# DIO_4.net
KiCad netlist of a schematic drawn in Altium Designer
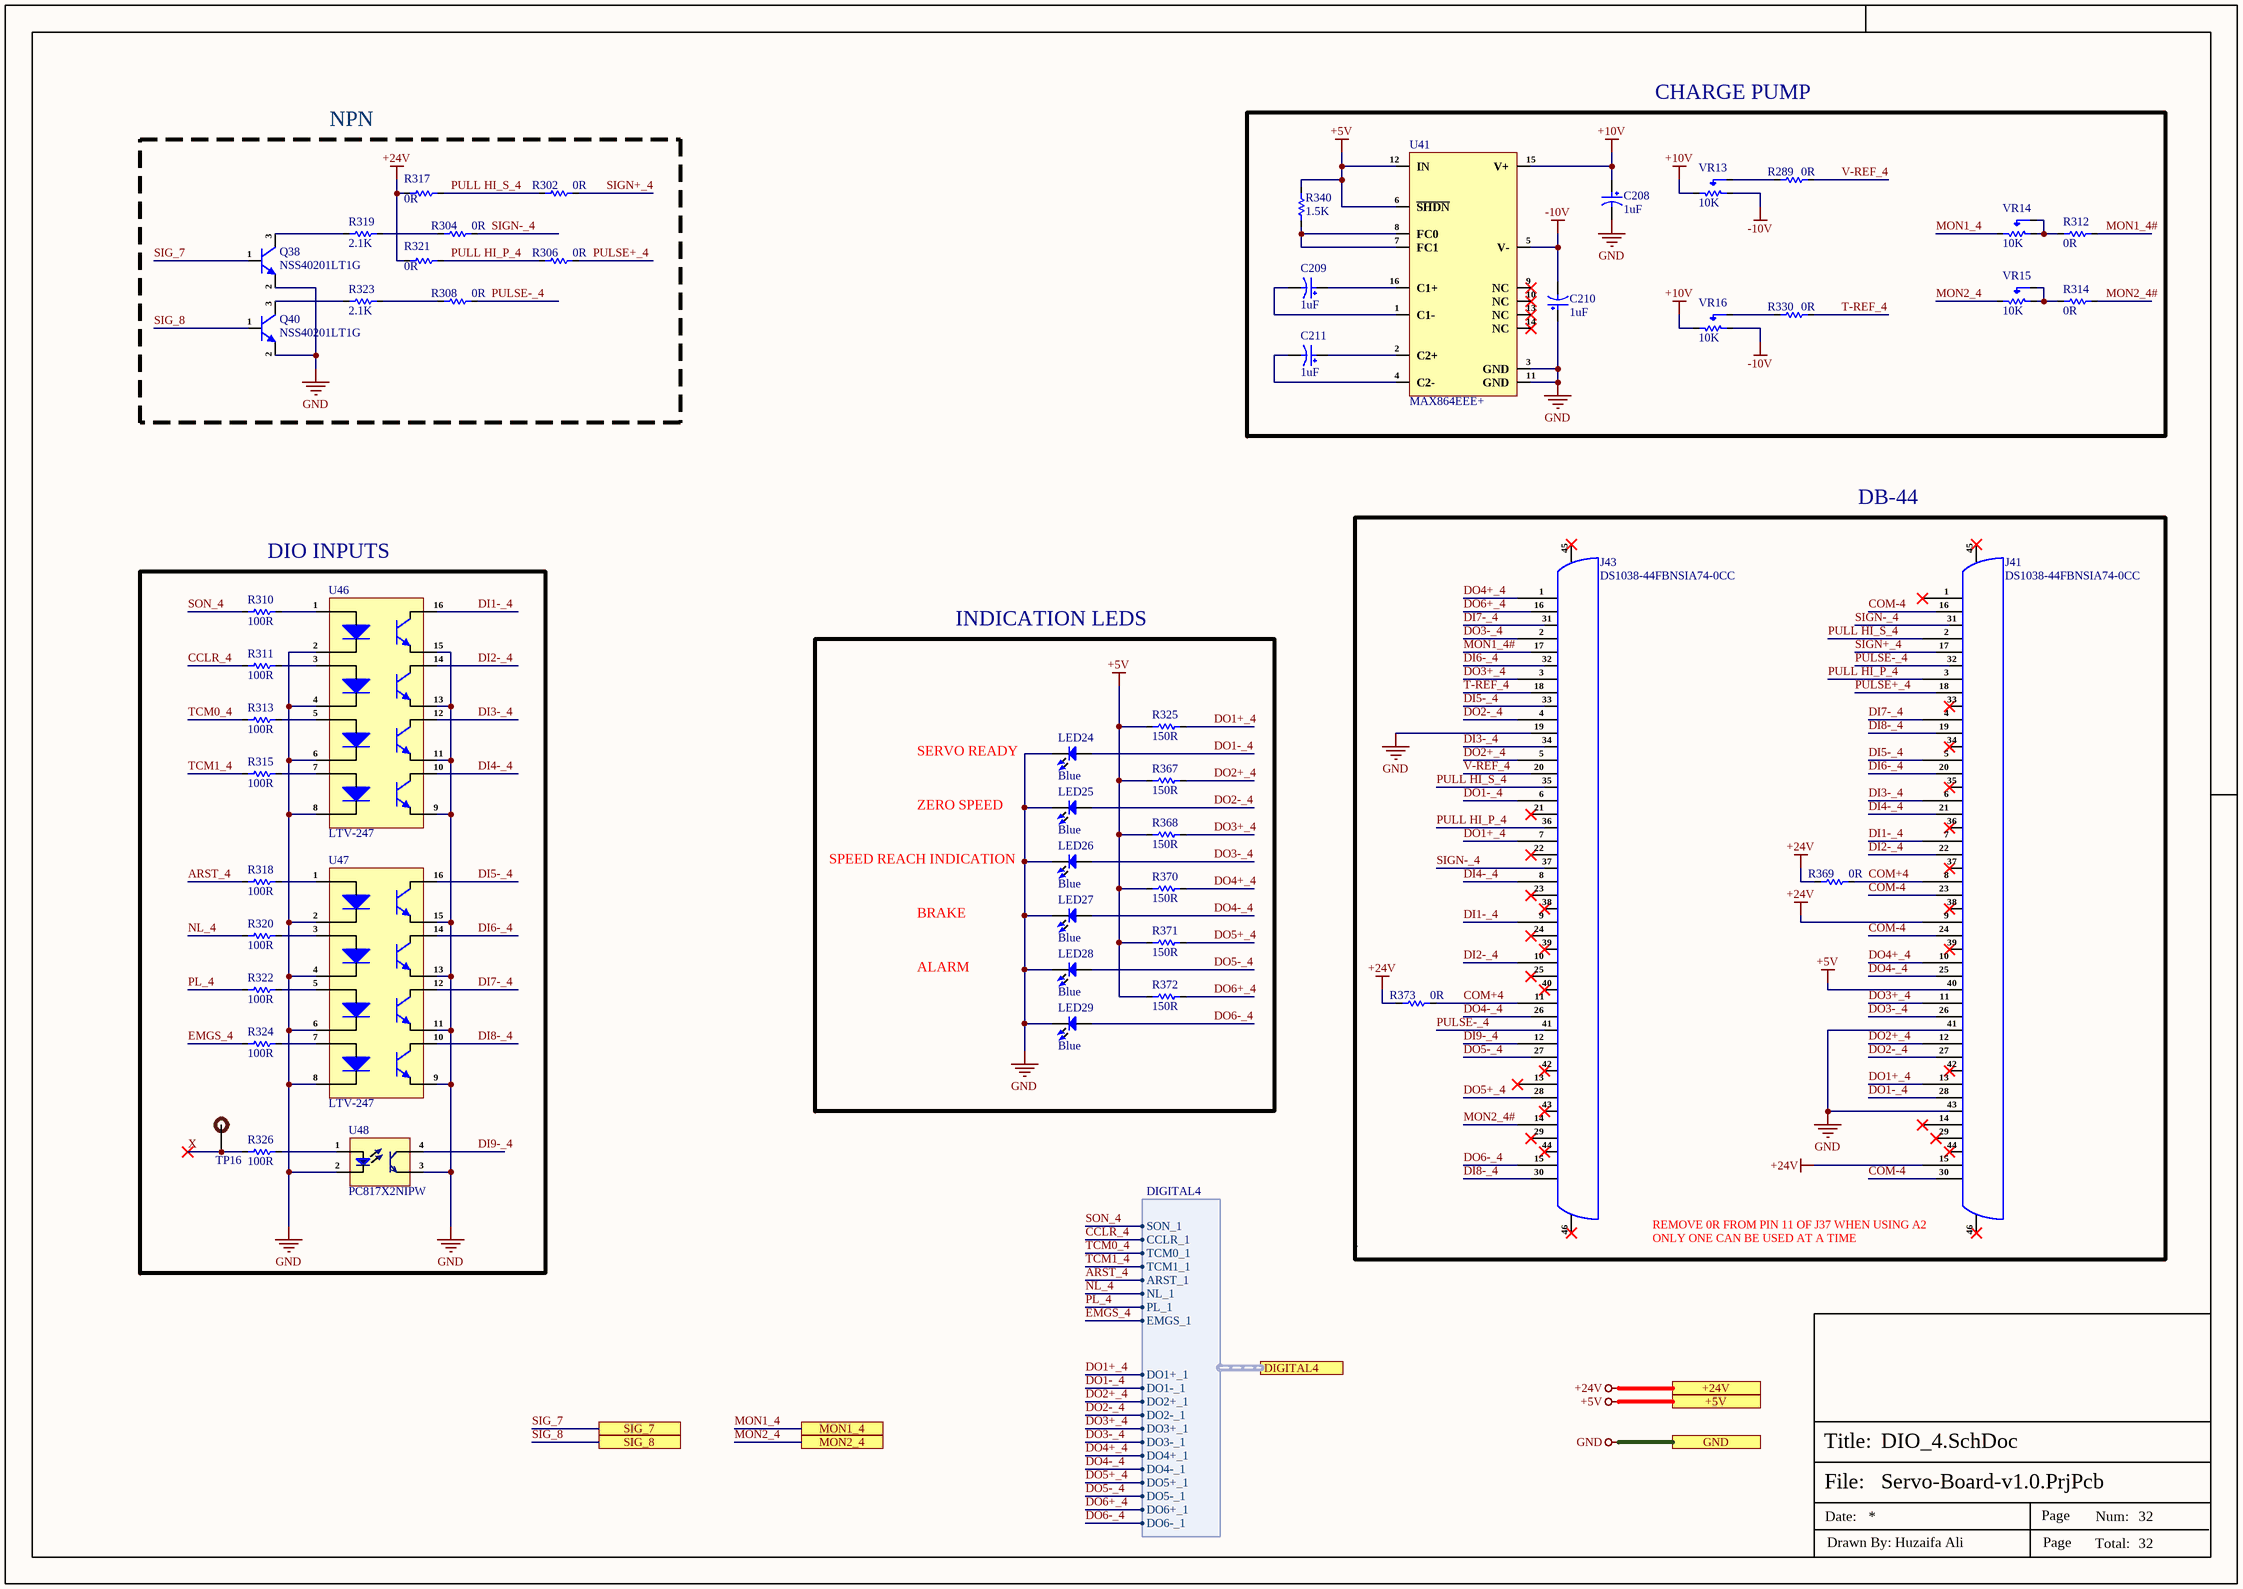
[diagram p0: DIO_4.SchDoc]

(export (version "E")
  (design (tool "Eeschema 10.0.6"))
  (components
    (comp (ref "C208")
      (value "1uF")
      (footprint "RVT1H1R0M0405")
      (description "1uF 50V 8mA@120Hz ±20% SMD,D4xL5.4mm Aluminum Electrolytic Capacitors - SMD ROHS")
      (fields (field (name "LCSC PART NUMBER") "C72491") (field (name "MANUFACTURER") "Roqang"))
      (libsource (lib "eSpark Libraries") (part "RVT1H1R0M0405"))
    )
    (comp (ref "C209")
      (value "1uF")
      (footprint "RVT1H1R0M0405")
      (description "1uF 50V 8mA@120Hz ±20% SMD,D4xL5.4mm Aluminum Electrolytic Capacitors - SMD ROHS")
      (fields (field (name "LCSC PART NUMBER") "C72491") (field (name "MANUFACTURER") "Roqang"))
      (libsource (lib "") (part "RVT1H1R0M0405_1"))
    )
    (comp (ref "C210")
      (value "1uF")
      (footprint "RVT1H1R0M0405")
      (description "1uF 50V 8mA@120Hz ±20% SMD,D4xL5.4mm Aluminum Electrolytic Capacitors - SMD ROHS")
      (fields (field (name "LCSC PART NUMBER") "C72491") (field (name "MANUFACTURER") "Roqang"))
      (libsource (lib "") (part "RVT1H1R0M0405_2"))
    )
    (comp (ref "C211")
      (value "1uF")
      (footprint "RVT1H1R0M0405")
      (description "1uF 50V 8mA@120Hz ±20% SMD,D4xL5.4mm Aluminum Electrolytic Capacitors - SMD ROHS")
      (fields (field (name "LCSC PART NUMBER") "C72491") (field (name "MANUFACTURER") "Roqang"))
      (libsource (lib "") (part "RVT1H1R0M0405_1"))
    )
    (comp (ref "J41")
      (value "DS1038-44FBNSIA74-0CC")
      (footprint "DS1038-44FBNSIA74-0CC")
      (description "44P Female D-Sub Right-Angle 3 1.5A -40℃~+105℃ Push-Pull D-Sub / VGA connector ROHS")
      (fields (field (name "MANUFACTURER") "CONNFLY Elec") (field (name "LCSC PART NUMBER") "C77844"))
      (libsource (lib "eSpark Libraries") (part "DS1038-44FBNSIA74-0CC"))
    )
    (comp (ref "J43")
      (value "DS1038-44FBNSIA74-0CC")
      (footprint "DS1038-44FBNSIA74-0CC")
      (description "44P Female D-Sub Right-Angle 3 1.5A -40℃~+105℃ Push-Pull D-Sub / VGA connector ROHS")
      (fields (field (name "MANUFACTURER") "CONNFLY Elec") (field (name "LCSC PART NUMBER") "C77844"))
      (libsource (lib "eSpark Libraries") (part "DS1038-44FBNSIA74-0CC"))
    )
    (comp (ref "LED24")
      (value "Blue")
      (footprint "LED-0603")
      (description "blue 0603 Light Emitting Diodes (LED) ROHS")
      (fields
        (field (name "MANUFACTURER") "Foshan NationStar Optoelectronics")
        (field (name "MANUFACTURER PART NUMBER") "NCD0603B3")
      )
      (libsource (lib "eSpark Libraries") (part "NCD0603B3"))
    )
    (comp (ref "LED25")
      (value "Blue")
      (footprint "LED-0603")
      (description "blue 0603 Light Emitting Diodes (LED) ROHS")
      (fields
        (field (name "MANUFACTURER") "Foshan NationStar Optoelectronics")
        (field (name "MANUFACTURER PART NUMBER") "NCD0603B3")
      )
      (libsource (lib "eSpark Libraries") (part "NCD0603B3"))
    )
    (comp (ref "LED26")
      (value "Blue")
      (footprint "LED-0603")
      (description "blue 0603 Light Emitting Diodes (LED) ROHS")
      (fields
        (field (name "MANUFACTURER") "Foshan NationStar Optoelectronics")
        (field (name "MANUFACTURER PART NUMBER") "NCD0603B3")
      )
      (libsource (lib "eSpark Libraries") (part "NCD0603B3"))
    )
    (comp (ref "LED27")
      (value "Blue")
      (footprint "LED-0603")
      (description "blue 0603 Light Emitting Diodes (LED) ROHS")
      (fields
        (field (name "MANUFACTURER") "Foshan NationStar Optoelectronics")
        (field (name "MANUFACTURER PART NUMBER") "NCD0603B3")
      )
      (libsource (lib "eSpark Libraries") (part "NCD0603B3"))
    )
    (comp (ref "LED28")
      (value "Blue")
      (footprint "LED-0603")
      (description "blue 0603 Light Emitting Diodes (LED) ROHS")
      (fields
        (field (name "MANUFACTURER") "Foshan NationStar Optoelectronics")
        (field (name "MANUFACTURER PART NUMBER") "NCD0603B3")
      )
      (libsource (lib "eSpark Libraries") (part "NCD0603B3"))
    )
    (comp (ref "LED29")
      (value "Blue")
      (footprint "LED-0603")
      (description "blue 0603 Light Emitting Diodes (LED) ROHS")
      (fields
        (field (name "MANUFACTURER") "Foshan NationStar Optoelectronics")
        (field (name "MANUFACTURER PART NUMBER") "NCD0603B3")
      )
      (libsource (lib "eSpark Libraries") (part "NCD0603B3"))
    )
    (comp (ref "Q38")
      (value "NSS40201LT1G")
      (footprint "SOT-23")
      (description "TRANS NPN 40V 2A SOT23-3")
      (fields (field (name "MANUFACTURER") "ON Semiconductor") (field (name "LCSC PART NUMBER") "C145175"))
      (libsource (lib "eSpark Libraries") (part "NSS40201LT1G"))
    )
    (comp (ref "Q40")
      (value "NSS40201LT1G")
      (footprint "SOT-23")
      (description "TRANS NPN 40V 2A SOT23-3")
      (fields (field (name "MANUFACTURER") "ON Semiconductor") (field (name "LCSC PART NUMBER") "C145175"))
      (libsource (lib "eSpark Libraries") (part "NSS40201LT1G"))
    )
    (comp (ref "R289")
      (value "0R")
      (footprint "Res-0402")
      (description "RES 0 OHM JUMPER 1/16W 0402")
      (fields
        (field (name "MANUFACTURER") "Yageo")
        (field (name "MANUFACTURER PART NUMBER") "RC0402FR-070RL")
      )
      (libsource (lib "eSpark Libraries") (part "RC0402FR-070RL"))
    )
    (comp (ref "R302")
      (value "0R")
      (footprint "Res-0603")
      (description "RES 0 OHM JUMPER 1/10W 0603")
      (fields
        (field (name "MANUFACTURER") "Yageo")
        (field (name "MANUFACTURER PART NUMBER") "RC0603JR-070RL")
      )
      (libsource (lib "eSpark Libraries") (part "RC0603JR-070RL"))
    )
    (comp (ref "R304")
      (value "0R")
      (footprint "Res-0603")
      (description "RES 0 OHM JUMPER 1/10W 0603")
      (fields
        (field (name "MANUFACTURER") "Yageo")
        (field (name "MANUFACTURER PART NUMBER") "RC0603JR-070RL")
      )
      (libsource (lib "eSpark Libraries") (part "RC0603JR-070RL"))
    )
    (comp (ref "R306")
      (value "0R")
      (footprint "Res-0603")
      (description "RES 0 OHM JUMPER 1/10W 0603")
      (fields
        (field (name "MANUFACTURER") "Yageo")
        (field (name "MANUFACTURER PART NUMBER") "RC0603JR-070RL")
      )
      (libsource (lib "eSpark Libraries") (part "RC0603JR-070RL"))
    )
    (comp (ref "R308")
      (value "0R")
      (footprint "Res-0603")
      (description "RES 0 OHM JUMPER 1/10W 0603")
      (fields
        (field (name "MANUFACTURER") "Yageo")
        (field (name "MANUFACTURER PART NUMBER") "RC0603JR-070RL")
      )
      (libsource (lib "eSpark Libraries") (part "RC0603JR-070RL"))
    )
    (comp (ref "R310")
      (value "100R")
      (footprint "Res-0402")
      (description "RES 100 OHM 1% 1/16W 0402")
      (fields
        (field (name "MANUFACTURER") "Yageo")
        (field (name "MANUFACTURER PART NUMBER") "RC0402FR-07100RL")
      )
      (libsource (lib "eSpark Libraries") (part "RC0402FR-07100RL"))
    )
    (comp (ref "R311")
      (value "100R")
      (footprint "Res-0402")
      (description "RES 100 OHM 1% 1/16W 0402")
      (fields
        (field (name "MANUFACTURER") "Yageo")
        (field (name "MANUFACTURER PART NUMBER") "RC0402FR-07100RL")
      )
      (libsource (lib "eSpark Libraries") (part "RC0402FR-07100RL"))
    )
    (comp (ref "R312")
      (value "0R")
      (footprint "Res-0402")
      (description "RES 0 OHM JUMPER 1/16W 0402")
      (fields
        (field (name "MANUFACTURER") "Yageo")
        (field (name "MANUFACTURER PART NUMBER") "RC0402FR-070RL")
      )
      (libsource (lib "eSpark Libraries") (part "RC0402FR-070RL"))
    )
    (comp (ref "R313")
      (value "100R")
      (footprint "Res-0402")
      (description "RES 100 OHM 1% 1/16W 0402")
      (fields
        (field (name "MANUFACTURER") "Yageo")
        (field (name "MANUFACTURER PART NUMBER") "RC0402FR-07100RL")
      )
      (libsource (lib "eSpark Libraries") (part "RC0402FR-07100RL"))
    )
    (comp (ref "R314")
      (value "0R")
      (footprint "Res-0402")
      (description "RES 0 OHM JUMPER 1/16W 0402")
      (fields
        (field (name "MANUFACTURER") "Yageo")
        (field (name "MANUFACTURER PART NUMBER") "RC0402FR-070RL")
      )
      (libsource (lib "eSpark Libraries") (part "RC0402FR-070RL"))
    )
    (comp (ref "R315")
      (value "100R")
      (footprint "Res-0402")
      (description "RES 100 OHM 1% 1/16W 0402")
      (fields
        (field (name "MANUFACTURER") "Yageo")
        (field (name "MANUFACTURER PART NUMBER") "RC0402FR-07100RL")
      )
      (libsource (lib "eSpark Libraries") (part "RC0402FR-07100RL"))
    )
    (comp (ref "R317")
      (value "0R")
      (footprint "Res-0603")
      (description "RES 0 OHM JUMPER 1/10W 0603")
      (fields
        (field (name "MANUFACTURER") "Yageo")
        (field (name "MANUFACTURER PART NUMBER") "RC0603JR-070RL")
      )
      (libsource (lib "eSpark Libraries") (part "RC0603JR-070RL"))
    )
    (comp (ref "R318")
      (value "100R")
      (footprint "Res-0402")
      (description "RES 100 OHM 1% 1/16W 0402")
      (fields
        (field (name "MANUFACTURER") "Yageo")
        (field (name "MANUFACTURER PART NUMBER") "RC0402FR-07100RL")
      )
      (libsource (lib "eSpark Libraries") (part "RC0402FR-07100RL"))
    )
    (comp (ref "R319")
      (value "2.1K")
      (footprint "Res-0603")
      (description "RES SMD 2.1K OHM 0.1% 1/10W 0603")
      (fields
        (field (name "MANUFACTURER") "Yageo")
        (field (name "MANUFACTURER PART NUMBER") "RT0603BRD072K1L")
      )
      (libsource (lib "eSpark Libraries") (part "RT0603BRD072K1L"))
    )
    (comp (ref "R320")
      (value "100R")
      (footprint "Res-0402")
      (description "RES 100 OHM 1% 1/16W 0402")
      (fields
        (field (name "MANUFACTURER") "Yageo")
        (field (name "MANUFACTURER PART NUMBER") "RC0402FR-07100RL")
      )
      (libsource (lib "eSpark Libraries") (part "RC0402FR-07100RL"))
    )
    (comp (ref "R321")
      (value "0R")
      (footprint "Res-0603")
      (description "RES 0 OHM JUMPER 1/10W 0603")
      (fields
        (field (name "MANUFACTURER") "Yageo")
        (field (name "MANUFACTURER PART NUMBER") "RC0603JR-070RL")
      )
      (libsource (lib "eSpark Libraries") (part "RC0603JR-070RL"))
    )
    (comp (ref "R322")
      (value "100R")
      (footprint "Res-0402")
      (description "RES 100 OHM 1% 1/16W 0402")
      (fields
        (field (name "MANUFACTURER") "Yageo")
        (field (name "MANUFACTURER PART NUMBER") "RC0402FR-07100RL")
      )
      (libsource (lib "eSpark Libraries") (part "RC0402FR-07100RL"))
    )
    (comp (ref "R323")
      (value "2.1K")
      (footprint "Res-0603")
      (description "RES SMD 2.1K OHM 0.1% 1/10W 0603")
      (fields
        (field (name "MANUFACTURER") "Yageo")
        (field (name "MANUFACTURER PART NUMBER") "RT0603BRD072K1L")
      )
      (libsource (lib "eSpark Libraries") (part "RT0603BRD072K1L"))
    )
    (comp (ref "R324")
      (value "100R")
      (footprint "Res-0402")
      (description "RES 100 OHM 1% 1/16W 0402")
      (fields
        (field (name "MANUFACTURER") "Yageo")
        (field (name "MANUFACTURER PART NUMBER") "RC0402FR-07100RL")
      )
      (libsource (lib "eSpark Libraries") (part "RC0402FR-07100RL"))
    )
    (comp (ref "R325")
      (value "150R")
      (footprint "Res-0603")
      (description "RES 150 OHM 0.5% 1/10W 0603")
      (fields
        (field (name "MANUFACTURER") "Yageo")
        (field (name "MANUFACTURER PART NUMBER") "RC0603DR-07150RL")
      )
      (libsource (lib "eSpark Libraries") (part "RC0603DR-07150RL"))
    )
    (comp (ref "R326")
      (value "100R")
      (footprint "Res-0402")
      (description "RES 100 OHM 1% 1/16W 0402")
      (fields
        (field (name "MANUFACTURER") "Yageo")
        (field (name "MANUFACTURER PART NUMBER") "RC0402FR-07100RL")
      )
      (libsource (lib "eSpark Libraries") (part "RC0402FR-07100RL"))
    )
    (comp (ref "R330")
      (value "0R")
      (footprint "Res-0402")
      (description "RES 0 OHM JUMPER 1/16W 0402")
      (fields
        (field (name "MANUFACTURER") "Yageo")
        (field (name "MANUFACTURER PART NUMBER") "RC0402FR-070RL")
      )
      (libsource (lib "eSpark Libraries") (part "RC0402FR-070RL"))
    )
    (comp (ref "R340")
      (value "1.5K")
      (footprint "Res-0402")
      (description "RES 1.5K OHM 1% 1/16W 0402")
      (fields
        (field (name "MANUFACTURER") "Yageo")
        (field (name "MANUFACTURER PART NUMBER") "RC0402FR-071K5L")
      )
      (libsource (lib "eSpark Libraries") (part "RC0402FR-071K5L"))
    )
    (comp (ref "R367")
      (value "150R")
      (footprint "Res-0603")
      (description "RES 150 OHM 0.5% 1/10W 0603")
      (fields
        (field (name "MANUFACTURER") "Yageo")
        (field (name "MANUFACTURER PART NUMBER") "RC0603DR-07150RL")
      )
      (libsource (lib "eSpark Libraries") (part "RC0603DR-07150RL"))
    )
    (comp (ref "R368")
      (value "150R")
      (footprint "Res-0603")
      (description "RES 150 OHM 0.5% 1/10W 0603")
      (fields
        (field (name "MANUFACTURER") "Yageo")
        (field (name "MANUFACTURER PART NUMBER") "RC0603DR-07150RL")
      )
      (libsource (lib "eSpark Libraries") (part "RC0603DR-07150RL"))
    )
    (comp (ref "R369")
      (value "0R")
      (footprint "Res-0402")
      (description "RES 0 OHM JUMPER 1/16W 0402")
      (fields
        (field (name "MANUFACTURER") "Yageo")
        (field (name "MANUFACTURER PART NUMBER") "RC0402FR-070RL")
      )
      (libsource (lib "eSpark Libraries") (part "RC0402FR-070RL"))
    )
    (comp (ref "R370")
      (value "150R")
      (footprint "Res-0603")
      (description "RES 150 OHM 0.5% 1/10W 0603")
      (fields
        (field (name "MANUFACTURER") "Yageo")
        (field (name "MANUFACTURER PART NUMBER") "RC0603DR-07150RL")
      )
      (libsource (lib "eSpark Libraries") (part "RC0603DR-07150RL"))
    )
    (comp (ref "R371")
      (value "150R")
      (footprint "Res-0603")
      (description "RES 150 OHM 0.5% 1/10W 0603")
      (fields
        (field (name "MANUFACTURER") "Yageo")
        (field (name "MANUFACTURER PART NUMBER") "RC0603DR-07150RL")
      )
      (libsource (lib "eSpark Libraries") (part "RC0603DR-07150RL"))
    )
    (comp (ref "R372")
      (value "150R")
      (footprint "Res-0603")
      (description "RES 150 OHM 0.5% 1/10W 0603")
      (fields
        (field (name "MANUFACTURER") "Yageo")
        (field (name "MANUFACTURER PART NUMBER") "RC0603DR-07150RL")
      )
      (libsource (lib "eSpark Libraries") (part "RC0603DR-07150RL"))
    )
    (comp (ref "R373")
      (value "0R")
      (footprint "Res-0402")
      (description "RES 0 OHM JUMPER 1/16W 0402")
      (fields
        (field (name "MANUFACTURER") "Yageo")
        (field (name "MANUFACTURER PART NUMBER") "RC0402FR-070RL")
      )
      (libsource (lib "eSpark Libraries") (part "RC0402FR-070RL"))
    )
    (comp (ref "TP16")
      (value "TEST POINT")
      (footprint "Test-point")
      (description "Test Point ON")
      (libsource (lib "eSpark Libraries") (part "TEST POINT"))
    )
    (comp (ref "U41")
      (value "MAX864EEE+")
      (footprint "16-QSOP")
      (description "IC REG CHARGE PUMP INV 16QSOP")
      (fields (field (name "MANUFACTURER") "Maxim"))
      (libsource (lib "eSpark Libraries") (part "MAX864EEE+"))
    )
    (comp (ref "U46")
      (value "LTV-247")
      (footprint "16-SO")
      (description "OPTOISO 3.75KV 4CH TRANS 16SO")
      (fields (field (name "MANUFACTURER") "Vishay Lite-On") (field (name "LCSC PART NUMBER") "C115451"))
      (libsource (lib "eSpark Libraries") (part "LTV-247"))
    )
    (comp (ref "U47")
      (value "LTV-247")
      (footprint "16-SO")
      (description "OPTOISO 3.75KV 4CH TRANS 16SO")
      (fields (field (name "MANUFACTURER") "Vishay Lite-On") (field (name "LCSC PART NUMBER") "C115451"))
      (libsource (lib "eSpark Libraries") (part "LTV-247"))
    )
    (comp (ref "U48")
      (value "PC817X2NIPW")
      (footprint "PC817X2NIPW")
      (description "Optoisolator Output Channel 4-SMD")
      (fields (field (name "MANUFACTURER") "Sharp") (field (name "LCSC PART NUMBER") "C2840443"))
      (libsource (lib "eSpark Libraries") (part "PC817X2NIPW"))
    )
    (comp (ref "VR13")
      (value "10K")
      (footprint "3362P-1-103")
      (description "TRIMMER 10K OHM 0.5W PC PIN TOP")
      (fields (field (name "LCSC PART NUMBER") "C118956") (field (name "MANUFACTURER") "Bourns"))
      (libsource (lib "eSpark Libraries") (part "3362P-1-103"))
    )
    (comp (ref "VR14")
      (value "10K")
      (footprint "3362P-1-103")
      (description "TRIMMER 10K OHM 0.5W PC PIN TOP")
      (fields (field (name "LCSC PART NUMBER") "C118956") (field (name "MANUFACTURER") "Bourns"))
      (libsource (lib "eSpark Libraries") (part "3362P-1-103"))
    )
    (comp (ref "VR15")
      (value "10K")
      (footprint "3362P-1-103")
      (description "TRIMMER 10K OHM 0.5W PC PIN TOP")
      (fields (field (name "LCSC PART NUMBER") "C118956") (field (name "MANUFACTURER") "Bourns"))
      (libsource (lib "eSpark Libraries") (part "3362P-1-103"))
    )
    (comp (ref "VR16")
      (value "10K")
      (footprint "3362P-1-103")
      (description "TRIMMER 10K OHM 0.5W PC PIN TOP")
      (fields (field (name "LCSC PART NUMBER") "C118956") (field (name "MANUFACTURER") "Bourns"))
      (libsource (lib "eSpark Libraries") (part "3362P-1-103"))
    )
  )
  (nets
    (net (code "2") (name "+5V") (class "Default")
      (node (ref "J41") (pin "40") (pinfunction "40_40") (pintype "passive"))
      (node (ref "R325") (pin "1") (pinfunction "1_1") (pintype "passive"))
      (node (ref "R340") (pin "2") (pinfunction "2_2") (pintype "passive"))
      (node (ref "R367") (pin "1") (pinfunction "1_1") (pintype "passive"))
      (node (ref "R368") (pin "1") (pinfunction "1_1") (pintype "passive"))
      (node (ref "R370") (pin "1") (pinfunction "1_1") (pintype "passive"))
      (node (ref "R371") (pin "1") (pinfunction "1_1") (pintype "passive"))
      (node (ref "R372") (pin "1") (pinfunction "1_1") (pintype "passive"))
      (node (ref "U41") (pin "12") (pinfunction "IN_12") (pintype "passive"))
      (node (ref "U41") (pin "6") (pinfunction "~{SHDN}_6") (pintype "passive"))
    )
    (net (code "3") (name "+10V") (class "Default")
      (node (ref "C208") (pin "1") (pintype "passive"))
      (node (ref "U41") (pin "15") (pinfunction "V+_15") (pintype "passive"))
      (node (ref "VR13") (pin "3") (pinfunction "CW_3") (pintype "passive"))
      (node (ref "VR16") (pin "3") (pinfunction "CW_3") (pintype "passive"))
    )
    (net (code "4") (name "+24V") (class "Default")
      (node (ref "J41") (pin "15") (pinfunction "15_15") (pintype "passive"))
      (node (ref "J41") (pin "9") (pinfunction "9_9") (pintype "passive"))
      (node (ref "R317") (pin "1") (pinfunction "1_1") (pintype "passive"))
      (node (ref "R321") (pin "1") (pinfunction "1_1") (pintype "passive"))
      (node (ref "R369") (pin "1") (pinfunction "1_1") (pintype "passive"))
      (node (ref "R373") (pin "1") (pinfunction "1_1") (pintype "passive"))
    )
    (net (code "5") (name "-10V") (class "Default")
      (node (ref "C210") (pin "2") (pintype "passive"))
      (node (ref "U41") (pin "5") (pinfunction "V-_5") (pintype "passive"))
      (node (ref "VR13") (pin "1") (pinfunction "CCW_1") (pintype "passive"))
      (node (ref "VR16") (pin "1") (pinfunction "CCW_1") (pintype "passive"))
    )
    (net (code "6") (name "/ARST_4") (class "Default")
      (node (ref "R318") (pin "1") (pinfunction "1_1") (pintype "passive"))
    )
    (net (code "7") (name "/CCLR_4") (class "Default")
      (node (ref "R311") (pin "1") (pinfunction "1_1") (pintype "passive"))
    )
    (net (code "8") (name "/COM+4") (class "Default")
      (node (ref "J41") (pin "8") (pinfunction "8_8") (pintype "passive"))
      (node (ref "J43") (pin "11") (pinfunction "11_11") (pintype "passive"))
      (node (ref "R369") (pin "2") (pinfunction "2_2") (pintype "passive"))
      (node (ref "R373") (pin "2") (pinfunction "2_2") (pintype "passive"))
    )
    (net (code "9") (name "/COM-4") (class "Default")
      (node (ref "J41") (pin "16") (pinfunction "16_16") (pintype "passive"))
      (node (ref "J41") (pin "23") (pinfunction "23_23") (pintype "passive"))
      (node (ref "J41") (pin "24") (pinfunction "24_24") (pintype "passive"))
      (node (ref "J41") (pin "30") (pinfunction "30_30") (pintype "passive"))
    )
    (net (code "10") (name "/DI1-_4") (class "Default")
      (node (ref "J41") (pin "7") (pinfunction "7_7") (pintype "passive"))
      (node (ref "J43") (pin "9") (pinfunction "9_9") (pintype "passive"))
      (node (ref "U46") (pin "16") (pinfunction "C_16") (pintype "passive"))
    )
    (net (code "11") (name "/DI2-_4") (class "Default")
      (node (ref "J41") (pin "22") (pinfunction "22_22") (pintype "passive"))
      (node (ref "J43") (pin "10") (pinfunction "10_10") (pintype "passive"))
      (node (ref "U46") (pin "14") (pinfunction "C_14") (pintype "passive"))
    )
    (net (code "12") (name "/DI3-_4") (class "Default")
      (node (ref "J41") (pin "6") (pinfunction "6_6") (pintype "passive"))
      (node (ref "J43") (pin "34") (pinfunction "34_34") (pintype "passive"))
      (node (ref "U46") (pin "12") (pinfunction "C_12") (pintype "passive"))
    )
    (net (code "13") (name "/DI4-_4") (class "Default")
      (node (ref "J41") (pin "21") (pinfunction "21_21") (pintype "passive"))
      (node (ref "J43") (pin "8") (pinfunction "8_8") (pintype "passive"))
      (node (ref "U46") (pin "10") (pinfunction "C_10") (pintype "passive"))
    )
    (net (code "14") (name "/DI5-_4") (class "Default")
      (node (ref "J41") (pin "5") (pinfunction "5_5") (pintype "passive"))
      (node (ref "J43") (pin "33") (pinfunction "33_33") (pintype "passive"))
      (node (ref "U47") (pin "16") (pinfunction "C_16") (pintype "passive"))
    )
    (net (code "15") (name "/DI6-_4") (class "Default")
      (node (ref "J41") (pin "20") (pinfunction "20_20") (pintype "passive"))
      (node (ref "J43") (pin "32") (pinfunction "32_32") (pintype "passive"))
      (node (ref "U47") (pin "14") (pinfunction "C_14") (pintype "passive"))
    )
    (net (code "16") (name "/DI7-_4") (class "Default")
      (node (ref "J41") (pin "4") (pinfunction "4_4") (pintype "passive"))
      (node (ref "J43") (pin "31") (pinfunction "31_31") (pintype "passive"))
      (node (ref "U47") (pin "12") (pinfunction "C_12") (pintype "passive"))
    )
    (net (code "17") (name "/DI8-_4") (class "Default")
      (node (ref "J41") (pin "19") (pinfunction "19_19") (pintype "passive"))
      (node (ref "J43") (pin "30") (pinfunction "30_30") (pintype "passive"))
      (node (ref "U47") (pin "10") (pinfunction "C_10") (pintype "passive"))
    )
    (net (code "18") (name "/DI9-_4") (class "Default")
      (node (ref "J43") (pin "12") (pinfunction "12_12") (pintype "passive"))
      (node (ref "U48") (pin "4") (pinfunction "C_4") (pintype "passive"))
    )
    (net (code "19") (name "/DO1+_4") (class "Default")
      (node (ref "J41") (pin "13") (pinfunction "13_13") (pintype "passive"))
      (node (ref "J43") (pin "7") (pinfunction "7_7") (pintype "passive"))
      (node (ref "R325") (pin "2") (pinfunction "2_2") (pintype "passive"))
    )
    (net (code "20") (name "/DO1-_4") (class "Default")
      (node (ref "J41") (pin "28") (pinfunction "28_28") (pintype "passive"))
      (node (ref "J43") (pin "6") (pinfunction "6_6") (pintype "passive"))
      (node (ref "LED24") (pin "1") (pinfunction "1_1") (pintype "passive"))
    )
    (net (code "21") (name "/DO2+_4") (class "Default")
      (node (ref "J41") (pin "12") (pinfunction "12_12") (pintype "passive"))
      (node (ref "J43") (pin "5") (pinfunction "5_5") (pintype "passive"))
      (node (ref "R367") (pin "2") (pinfunction "2_2") (pintype "passive"))
    )
    (net (code "22") (name "/DO2-_4") (class "Default")
      (node (ref "J41") (pin "27") (pinfunction "27_27") (pintype "passive"))
      (node (ref "J43") (pin "4") (pinfunction "4_4") (pintype "passive"))
      (node (ref "LED25") (pin "1") (pinfunction "1_1") (pintype "passive"))
    )
    (net (code "23") (name "/DO3+_4") (class "Default")
      (node (ref "J41") (pin "11") (pinfunction "11_11") (pintype "passive"))
      (node (ref "J43") (pin "3") (pinfunction "3_3") (pintype "passive"))
      (node (ref "R368") (pin "2") (pinfunction "2_2") (pintype "passive"))
    )
    (net (code "24") (name "/DO3-_4") (class "Default")
      (node (ref "J41") (pin "26") (pinfunction "26_26") (pintype "passive"))
      (node (ref "J43") (pin "2") (pinfunction "2_2") (pintype "passive"))
      (node (ref "LED26") (pin "1") (pinfunction "1_1") (pintype "passive"))
    )
    (net (code "25") (name "/DO4+_4") (class "Default")
      (node (ref "J41") (pin "10") (pinfunction "10_10") (pintype "passive"))
      (node (ref "J43") (pin "1") (pinfunction "1_1") (pintype "passive"))
      (node (ref "R370") (pin "2") (pinfunction "2_2") (pintype "passive"))
    )
    (net (code "26") (name "/DO4-_4") (class "Default")
      (node (ref "J41") (pin "25") (pinfunction "25_25") (pintype "passive"))
      (node (ref "J43") (pin "26") (pinfunction "26_26") (pintype "passive"))
      (node (ref "LED27") (pin "1") (pinfunction "1_1") (pintype "passive"))
    )
    (net (code "27") (name "/DO5+_4") (class "Default")
      (node (ref "J43") (pin "28") (pinfunction "28_28") (pintype "passive"))
      (node (ref "R371") (pin "2") (pinfunction "2_2") (pintype "passive"))
    )
    (net (code "28") (name "/DO5-_4") (class "Default")
      (node (ref "J43") (pin "27") (pinfunction "27_27") (pintype "passive"))
      (node (ref "LED28") (pin "1") (pinfunction "1_1") (pintype "passive"))
    )
    (net (code "29") (name "/DO6+_4") (class "Default")
      (node (ref "J43") (pin "16") (pinfunction "16_16") (pintype "passive"))
      (node (ref "R372") (pin "2") (pinfunction "2_2") (pintype "passive"))
    )
    (net (code "30") (name "/DO6-_4") (class "Default")
      (node (ref "J43") (pin "15") (pinfunction "15_15") (pintype "passive"))
      (node (ref "LED29") (pin "1") (pinfunction "1_1") (pintype "passive"))
    )
    (net (code "31") (name "/EMGS_4") (class "Default")
      (node (ref "R324") (pin "1") (pinfunction "1_1") (pintype "passive"))
    )
    (net (code "32") (name "/MON1_4") (class "Default")
      (node (ref "VR14") (pin "3") (pinfunction "CW_3") (pintype "passive"))
    )
    (net (code "33") (name "/MON1_4#") (class "Default")
      (node (ref "J43") (pin "17") (pinfunction "17_17") (pintype "passive"))
      (node (ref "R312") (pin "2") (pinfunction "2_2") (pintype "passive"))
    )
    (net (code "34") (name "/MON2_4") (class "Default")
      (node (ref "VR15") (pin "3") (pinfunction "CW_3") (pintype "passive"))
    )
    (net (code "35") (name "/MON2_4#") (class "Default")
      (node (ref "J43") (pin "14") (pinfunction "14_14") (pintype "passive"))
      (node (ref "R314") (pin "2") (pinfunction "2_2") (pintype "passive"))
    )
    (net (code "36") (name "/NL_4") (class "Default")
      (node (ref "R320") (pin "1") (pinfunction "1_1") (pintype "passive"))
    )
    (net (code "37") (name "/PL_4") (class "Default")
      (node (ref "R322") (pin "1") (pinfunction "1_1") (pintype "passive"))
    )
    (net (code "38") (name "/PULL HI_P_4") (class "Default")
      (node (ref "J41") (pin "3") (pinfunction "3_3") (pintype "passive"))
      (node (ref "J43") (pin "36") (pinfunction "36_36") (pintype "passive"))
      (node (ref "R306") (pin "1") (pinfunction "1_1") (pintype "passive"))
      (node (ref "R321") (pin "2") (pinfunction "2_2") (pintype "passive"))
    )
    (net (code "39") (name "/PULL HI_S_4") (class "Default")
      (node (ref "J41") (pin "2") (pinfunction "2_2") (pintype "passive"))
      (node (ref "J43") (pin "35") (pinfunction "35_35") (pintype "passive"))
      (node (ref "R302") (pin "1") (pinfunction "1_1") (pintype "passive"))
      (node (ref "R317") (pin "2") (pinfunction "2_2") (pintype "passive"))
    )
    (net (code "40") (name "/PULSE+_4") (class "Default")
      (node (ref "J41") (pin "18") (pinfunction "18_18") (pintype "passive"))
      (node (ref "R306") (pin "2") (pinfunction "2_2") (pintype "passive"))
    )
    (net (code "41") (name "/PULSE-_4") (class "Default")
      (node (ref "J41") (pin "32") (pinfunction "32_32") (pintype "passive"))
      (node (ref "J43") (pin "41") (pinfunction "41_41") (pintype "passive"))
      (node (ref "R308") (pin "2") (pinfunction "2_2") (pintype "passive"))
    )
    (net (code "42") (name "/SIGN+_4") (class "Default")
      (node (ref "J41") (pin "17") (pinfunction "17_17") (pintype "passive"))
      (node (ref "R302") (pin "2") (pinfunction "2_2") (pintype "passive"))
    )
    (net (code "43") (name "/SIGN-_4") (class "Default")
      (node (ref "J41") (pin "31") (pinfunction "31_31") (pintype "passive"))
      (node (ref "J43") (pin "37") (pinfunction "37_37") (pintype "passive"))
      (node (ref "R304") (pin "2") (pinfunction "2_2") (pintype "passive"))
    )
    (net (code "44") (name "/SIG_7") (class "Default")
      (node (ref "Q38") (pin "1") (pinfunction "B_1") (pintype "passive"))
    )
    (net (code "45") (name "/SIG_8") (class "Default")
      (node (ref "Q40") (pin "1") (pinfunction "B_1") (pintype "passive"))
    )
    (net (code "46") (name "/SON_4") (class "Default")
      (node (ref "R310") (pin "1") (pinfunction "1_1") (pintype "passive"))
    )
    (net (code "47") (name "/T-REF_4") (class "Default")
      (node (ref "J43") (pin "18") (pinfunction "18_18") (pintype "passive"))
      (node (ref "R330") (pin "2") (pinfunction "2_2") (pintype "passive"))
    )
    (net (code "48") (name "/TCM0_4") (class "Default")
      (node (ref "R313") (pin "1") (pinfunction "1_1") (pintype "passive"))
    )
    (net (code "49") (name "/TCM1_4") (class "Default")
      (node (ref "R315") (pin "1") (pinfunction "1_1") (pintype "passive"))
    )
    (net (code "50") (name "/V-REF_4") (class "Default")
      (node (ref "J43") (pin "20") (pinfunction "20_20") (pintype "passive"))
      (node (ref "R289") (pin "2") (pinfunction "2_2") (pintype "passive"))
    )
    (net (code "51") (name "/X") (class "Default")
      (node (ref "R326") (pin "1") (pinfunction "1_1") (pintype "passive"))
      (node (ref "TP16") (pin "1") (pinfunction "1_1") (pintype "passive"))
    )
    (net (code "53") (name "GND") (class "Default")
      (node (ref "C208") (pin "2") (pintype "passive"))
      (node (ref "C210") (pin "1") (pintype "passive"))
      (node (ref "J41") (pin "41") (pinfunction "41_41") (pintype "passive"))
      (node (ref "J41") (pin "43") (pinfunction "43_43") (pintype "passive"))
      (node (ref "J43") (pin "19") (pinfunction "19_19") (pintype "passive"))
      (node (ref "LED24") (pin "2") (pinfunction "2_2") (pintype "passive"))
      (node (ref "LED25") (pin "2") (pinfunction "2_2") (pintype "passive"))
      (node (ref "LED26") (pin "2") (pinfunction "2_2") (pintype "passive"))
      (node (ref "LED27") (pin "2") (pinfunction "2_2") (pintype "passive"))
      (node (ref "LED28") (pin "2") (pinfunction "2_2") (pintype "passive"))
      (node (ref "LED29") (pin "2") (pinfunction "2_2") (pintype "passive"))
      (node (ref "Q38") (pin "2") (pinfunction "E_2") (pintype "passive"))
      (node (ref "Q40") (pin "2") (pinfunction "E_2") (pintype "passive"))
      (node (ref "U41") (pin "11") (pinfunction "GND_11") (pintype "passive"))
      (node (ref "U41") (pin "3") (pinfunction "GND_3") (pintype "passive"))
      (node (ref "U46") (pin "11") (pinfunction "E_11") (pintype "passive"))
      (node (ref "U46") (pin "13") (pinfunction "E_13") (pintype "passive"))
      (node (ref "U46") (pin "15") (pinfunction "E_15") (pintype "passive"))
      (node (ref "U46") (pin "2") (pinfunction "K_2") (pintype "passive"))
      (node (ref "U46") (pin "4") (pinfunction "K_4") (pintype "passive"))
      (node (ref "U46") (pin "6") (pinfunction "K_6") (pintype "passive"))
      (node (ref "U46") (pin "8") (pinfunction "K_8") (pintype "passive"))
      (node (ref "U46") (pin "9") (pinfunction "E_9") (pintype "passive"))
      (node (ref "U47") (pin "11") (pinfunction "E_11") (pintype "passive"))
      (node (ref "U47") (pin "13") (pinfunction "E_13") (pintype "passive"))
      (node (ref "U47") (pin "15") (pinfunction "E_15") (pintype "passive"))
      (node (ref "U47") (pin "2") (pinfunction "K_2") (pintype "passive"))
      (node (ref "U47") (pin "4") (pinfunction "K_4") (pintype "passive"))
      (node (ref "U47") (pin "6") (pinfunction "K_6") (pintype "passive"))
      (node (ref "U47") (pin "8") (pinfunction "K_8") (pintype "passive"))
      (node (ref "U47") (pin "9") (pinfunction "E_9") (pintype "passive"))
      (node (ref "U48") (pin "2") (pinfunction "Ca_2") (pintype "passive"))
      (node (ref "U48") (pin "3") (pinfunction "E_3") (pintype "passive"))
    )
    (net (code "54") (name "Net-(Q38-C)") (class "Default")
      (node (ref "Q38") (pin "3") (pinfunction "C_3") (pintype "passive"))
      (node (ref "R319") (pin "1") (pinfunction "1_1") (pintype "passive"))
    )
    (net (code "55") (name "Net-(Q40-C)") (class "Default")
      (node (ref "Q40") (pin "3") (pinfunction "C_3") (pintype "passive"))
      (node (ref "R323") (pin "1") (pinfunction "1_1") (pintype "passive"))
    )
    (net (code "56") (name "Net-(R304-Pad1)") (class "Default")
      (node (ref "R304") (pin "1") (pinfunction "1_1") (pintype "passive"))
      (node (ref "R319") (pin "2") (pinfunction "2_2") (pintype "passive"))
    )
    (net (code "57") (name "Net-(R308-Pad1)") (class "Default")
      (node (ref "R308") (pin "1") (pinfunction "1_1") (pintype "passive"))
      (node (ref "R323") (pin "2") (pinfunction "2_2") (pintype "passive"))
    )
    (net (code "58") (name "Net-(R310-Pad2)") (class "Default")
      (node (ref "R310") (pin "2") (pinfunction "2_2") (pintype "passive"))
      (node (ref "U46") (pin "1") (pinfunction "A_1") (pintype "passive"))
    )
    (net (code "59") (name "Net-(R311-Pad2)") (class "Default")
      (node (ref "R311") (pin "2") (pinfunction "2_2") (pintype "passive"))
      (node (ref "U46") (pin "3") (pinfunction "A_3") (pintype "passive"))
    )
    (net (code "60") (name "Net-(R313-Pad2)") (class "Default")
      (node (ref "R313") (pin "2") (pinfunction "2_2") (pintype "passive"))
      (node (ref "U46") (pin "5") (pinfunction "A_5") (pintype "passive"))
    )
    (net (code "61") (name "Net-(R315-Pad2)") (class "Default")
      (node (ref "R315") (pin "2") (pinfunction "2_2") (pintype "passive"))
      (node (ref "U46") (pin "7") (pinfunction "A_7") (pintype "passive"))
    )
    (net (code "62") (name "Net-(R318-Pad2)") (class "Default")
      (node (ref "R318") (pin "2") (pinfunction "2_2") (pintype "passive"))
      (node (ref "U47") (pin "1") (pinfunction "A_1") (pintype "passive"))
    )
    (net (code "63") (name "Net-(R320-Pad2)") (class "Default")
      (node (ref "R320") (pin "2") (pinfunction "2_2") (pintype "passive"))
      (node (ref "U47") (pin "3") (pinfunction "A_3") (pintype "passive"))
    )
    (net (code "64") (name "Net-(R322-Pad2)") (class "Default")
      (node (ref "R322") (pin "2") (pinfunction "2_2") (pintype "passive"))
      (node (ref "U47") (pin "5") (pinfunction "A_5") (pintype "passive"))
    )
    (net (code "65") (name "Net-(R324-Pad2)") (class "Default")
      (node (ref "R324") (pin "2") (pinfunction "2_2") (pintype "passive"))
      (node (ref "U47") (pin "7") (pinfunction "A_7") (pintype "passive"))
    )
    (net (code "66") (name "Net-(U41-C1+)") (class "Default")
      (node (ref "C209") (pin "1") (pintype "passive"))
      (node (ref "U41") (pin "16") (pinfunction "C1+_16") (pintype "passive"))
    )
    (net (code "67") (name "Net-(U41-C1-)") (class "Default")
      (node (ref "C209") (pin "2") (pintype "passive"))
      (node (ref "U41") (pin "1") (pinfunction "C1-_1") (pintype "passive"))
    )
    (net (code "68") (name "Net-(U41-C2+)") (class "Default")
      (node (ref "C211") (pin "1") (pintype "passive"))
      (node (ref "U41") (pin "2") (pinfunction "C2+_2") (pintype "passive"))
    )
    (net (code "69") (name "Net-(U41-C2-)") (class "Default")
      (node (ref "C211") (pin "2") (pintype "passive"))
      (node (ref "U41") (pin "4") (pinfunction "C2-_4") (pintype "passive"))
    )
    (net (code "70") (name "Net-(U41-FC0)") (class "Default")
      (node (ref "R340") (pin "1") (pinfunction "1_1") (pintype "passive"))
      (node (ref "U41") (pin "7") (pinfunction "FC1_7") (pintype "passive"))
      (node (ref "U41") (pin "8") (pinfunction "FC0_8") (pintype "passive"))
    )
    (net (code "71") (name "Net-(U48-An)") (class "Default")
      (node (ref "R326") (pin "2") (pinfunction "2_2") (pintype "passive"))
      (node (ref "U48") (pin "1") (pinfunction "An_1") (pintype "passive"))
    )
    (net (code "72") (name "Net-(VR13-Wiper)") (class "Default")
      (node (ref "R289") (pin "1") (pinfunction "1_1") (pintype "passive"))
      (node (ref "VR13") (pin "2") (pinfunction "Wiper_2") (pintype "passive"))
    )
    (net (code "73") (name "Net-(VR14-CCW)") (class "Default")
      (node (ref "R312") (pin "1") (pinfunction "1_1") (pintype "passive"))
      (node (ref "VR14") (pin "1") (pinfunction "CCW_1") (pintype "passive"))
      (node (ref "VR14") (pin "2") (pinfunction "Wiper_2") (pintype "passive"))
    )
    (net (code "74") (name "Net-(VR15-CCW)") (class "Default")
      (node (ref "R314") (pin "1") (pinfunction "1_1") (pintype "passive"))
      (node (ref "VR15") (pin "1") (pinfunction "CCW_1") (pintype "passive"))
      (node (ref "VR15") (pin "2") (pinfunction "Wiper_2") (pintype "passive"))
    )
    (net (code "75") (name "Net-(VR16-Wiper)") (class "Default")
      (node (ref "R330") (pin "1") (pinfunction "1_1") (pintype "passive"))
      (node (ref "VR16") (pin "2") (pinfunction "Wiper_2") (pintype "passive"))
    )
    (net (code "76") (name "unconnected-(J41-Pad1)") (class "Default")
      (node (ref "J41") (pin "1") (pinfunction "1_1") (pintype "passive+no_connect"))
    )
    (net (code "77") (name "unconnected-(J41-Pad14)") (class "Default")
      (node (ref "J41") (pin "14") (pinfunction "14_14") (pintype "passive+no_connect"))
    )
    (net (code "78") (name "unconnected-(J41-Pad29)") (class "Default")
      (node (ref "J41") (pin "29") (pinfunction "29_29") (pintype "passive+no_connect"))
    )
    (net (code "79") (name "unconnected-(J41-Pad33)") (class "Default")
      (node (ref "J41") (pin "33") (pinfunction "33_33") (pintype "passive+no_connect"))
    )
    (net (code "80") (name "unconnected-(J41-Pad34)") (class "Default")
      (node (ref "J41") (pin "34") (pinfunction "34_34") (pintype "passive+no_connect"))
    )
    (net (code "81") (name "unconnected-(J41-Pad35)") (class "Default")
      (node (ref "J41") (pin "35") (pinfunction "35_35") (pintype "passive+no_connect"))
    )
    (net (code "82") (name "unconnected-(J41-Pad36)") (class "Default")
      (node (ref "J41") (pin "36") (pinfunction "36_36") (pintype "passive+no_connect"))
    )
    (net (code "83") (name "unconnected-(J41-Pad37)") (class "Default")
      (node (ref "J41") (pin "37") (pinfunction "37_37") (pintype "passive+no_connect"))
    )
    (net (code "84") (name "unconnected-(J41-Pad38)") (class "Default")
      (node (ref "J41") (pin "38") (pinfunction "38_38") (pintype "passive+no_connect"))
    )
    (net (code "85") (name "unconnected-(J41-Pad39)") (class "Default")
      (node (ref "J41") (pin "39") (pinfunction "39_39") (pintype "passive+no_connect"))
    )
    (net (code "86") (name "unconnected-(J41-Pad42)") (class "Default")
      (node (ref "J41") (pin "42") (pinfunction "42_42") (pintype "passive+no_connect"))
    )
    (net (code "87") (name "unconnected-(J41-Pad44)") (class "Default")
      (node (ref "J41") (pin "44") (pinfunction "44_44") (pintype "passive+no_connect"))
    )
    (net (code "88") (name "unconnected-(J41-Pad45)") (class "Default")
      (node (ref "J41") (pin "45") (pinfunction "45_45") (pintype "passive+no_connect"))
    )
    (net (code "89") (name "unconnected-(J41-Pad46)") (class "Default")
      (node (ref "J41") (pin "46") (pinfunction "46_46") (pintype "passive+no_connect"))
    )
    (net (code "90") (name "unconnected-(J43-Pad13)") (class "Default")
      (node (ref "J43") (pin "13") (pinfunction "13_13") (pintype "passive+no_connect"))
    )
    (net (code "91") (name "unconnected-(J43-Pad21)") (class "Default")
      (node (ref "J43") (pin "21") (pinfunction "21_21") (pintype "passive+no_connect"))
    )
    (net (code "92") (name "unconnected-(J43-Pad22)") (class "Default")
      (node (ref "J43") (pin "22") (pinfunction "22_22") (pintype "passive+no_connect"))
    )
    (net (code "93") (name "unconnected-(J43-Pad23)") (class "Default")
      (node (ref "J43") (pin "23") (pinfunction "23_23") (pintype "passive+no_connect"))
    )
    (net (code "94") (name "unconnected-(J43-Pad24)") (class "Default")
      (node (ref "J43") (pin "24") (pinfunction "24_24") (pintype "passive+no_connect"))
    )
    (net (code "95") (name "unconnected-(J43-Pad25)") (class "Default")
      (node (ref "J43") (pin "25") (pinfunction "25_25") (pintype "passive+no_connect"))
    )
    (net (code "96") (name "unconnected-(J43-Pad29)") (class "Default")
      (node (ref "J43") (pin "29") (pinfunction "29_29") (pintype "passive+no_connect"))
    )
    (net (code "97") (name "unconnected-(J43-Pad38)") (class "Default")
      (node (ref "J43") (pin "38") (pinfunction "38_38") (pintype "passive+no_connect"))
    )
    (net (code "98") (name "unconnected-(J43-Pad39)") (class "Default")
      (node (ref "J43") (pin "39") (pinfunction "39_39") (pintype "passive+no_connect"))
    )
    (net (code "99") (name "unconnected-(J43-Pad40)") (class "Default")
      (node (ref "J43") (pin "40") (pinfunction "40_40") (pintype "passive+no_connect"))
    )
    (net (code "100") (name "unconnected-(J43-Pad42)") (class "Default")
      (node (ref "J43") (pin "42") (pinfunction "42_42") (pintype "passive+no_connect"))
    )
    (net (code "101") (name "unconnected-(J43-Pad43)") (class "Default")
      (node (ref "J43") (pin "43") (pinfunction "43_43") (pintype "passive+no_connect"))
    )
    (net (code "102") (name "unconnected-(J43-Pad44)") (class "Default")
      (node (ref "J43") (pin "44") (pinfunction "44_44") (pintype "passive+no_connect"))
    )
    (net (code "103") (name "unconnected-(J43-Pad45)") (class "Default")
      (node (ref "J43") (pin "45") (pinfunction "45_45") (pintype "passive+no_connect"))
    )
    (net (code "104") (name "unconnected-(J43-Pad46)") (class "Default")
      (node (ref "J43") (pin "46") (pinfunction "46_46") (pintype "passive+no_connect"))
    )
    (net (code "105") (name "unconnected-(U41-NC-Pad9)") (class "Default")
      (node (ref "U41") (pin "9") (pinfunction "NC_9") (pintype "passive+no_connect"))
    )
    (net (code "106") (name "unconnected-(U41-NC-Pad10)") (class "Default")
      (node (ref "U41") (pin "10") (pinfunction "NC_10") (pintype "passive+no_connect"))
    )
    (net (code "107") (name "unconnected-(U41-NC-Pad13)") (class "Default")
      (node (ref "U41") (pin "13") (pinfunction "NC_13") (pintype "passive+no_connect"))
    )
    (net (code "108") (name "unconnected-(U41-NC-Pad14)") (class "Default")
      (node (ref "U41") (pin "14") (pinfunction "NC_14") (pintype "passive+no_connect"))
    )
  )
)
